# implant9.net
KiCad netlist of a schematic drawn in EAGLE
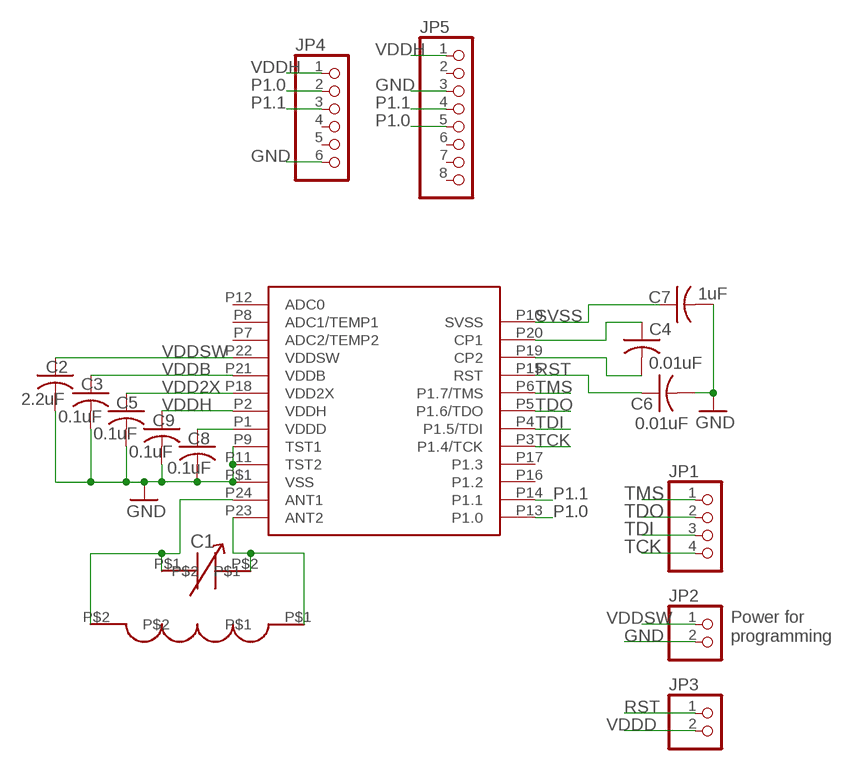
[diagram p0: schematic, sheet 1]

(export (version "E")
  (design (tool "Eeschema 10.0.6"))
  (components
    (comp (ref "C2")
      (value "2.2uF")
      (footprint "eagle-import:C0805")
      (libsource (lib "eagle-import") (part "C-USC0805"))
    )
    (comp (ref "C3")
      (value "0.1uF")
      (footprint "eagle-import:C0805")
      (libsource (lib "eagle-import") (part "C-USC0805"))
    )
    (comp (ref "C4")
      (value "0.01uF")
      (footprint "eagle-import:C0805")
      (libsource (lib "eagle-import") (part "C-USC0805"))
    )
    (comp (ref "C5")
      (value "0.1uF")
      (footprint "eagle-import:C0805")
      (libsource (lib "eagle-import") (part "C-USC0805"))
    )
    (comp (ref "C6")
      (value "0.01uF")
      (footprint "eagle-import:C0805")
      (libsource (lib "eagle-import") (part "C-USC0805"))
    )
    (comp (ref "C7")
      (value "1uF")
      (footprint "eagle-import:C0805")
      (libsource (lib "eagle-import") (part "C-USC0805"))
    )
    (comp (ref "C8")
      (value "0.1uF")
      (footprint "eagle-import:C0805")
      (libsource (lib "eagle-import") (part "C-USC0805"))
    )
    (comp (ref "C9")
      (value "0.1uF")
      (footprint "eagle-import:C0805")
      (libsource (lib "eagle-import") (part "C-USC0805"))
    )
    (comp (ref "JP1")
      (value "PINHD-1X4")
      (footprint "eagle-import:1X04")
      (libsource (lib "eagle-import") (part "PINHD-1X4"))
    )
    (comp (ref "JP2")
      (value "PINHD-1X2")
      (footprint "eagle-import:1X02")
      (libsource (lib "eagle-import") (part "PINHD-1X2"))
    )
    (comp (ref "JP3")
      (value "PINHD-1X2")
      (footprint "eagle-import:1X02")
      (libsource (lib "eagle-import") (part "PINHD-1X2"))
    )
    (comp (ref "JP4")
      (value "PINHD-1X6")
      (footprint "eagle-import:1X06")
      (libsource (lib "eagle-import") (part "PINHD-1X6"))
    )
    (comp (ref "JP5")
      (value "PINHD-1X8")
      (footprint "eagle-import:1X08")
      (libsource (lib "eagle-import") (part "PINHD-1X8"))
    )
    (comp (ref "U$1")
      (value "RF430FRL152H")
      (footprint "eagle-import:VQFN")
      (libsource (lib "eagle-import") (part "RF430FRL152H"))
    )
    (comp (ref "U$2")
      (value "COILCOIL3")
      (footprint "eagle-import:COIL3")
      (libsource (lib "eagle-import") (part "COILCOIL3"))
    )
    (comp (ref "U$3")
      (value "VAR_CAP")
      (footprint "eagle-import:VAR_CAP")
      (libsource (lib "eagle-import") (part "VAR_CAP"))
    )
  )
  (nets
    (net (code "1") (name "/P1.0") (class "Default")
      (node (ref "JP4") (pin "2") (pinfunction "2_2") (pintype "passive"))
      (node (ref "JP5") (pin "5") (pinfunction "5_5") (pintype "passive"))
      (node (ref "U$1") (pin "P13") (pinfunction "P1.0_P13") (pintype "bidirectional"))
    )
    (net (code "2") (name "/P1.1") (class "Default")
      (node (ref "JP4") (pin "3") (pinfunction "3_3") (pintype "passive"))
      (node (ref "JP5") (pin "4") (pinfunction "4_4") (pintype "passive"))
      (node (ref "U$1") (pin "P14") (pinfunction "P1.1_P14") (pintype "bidirectional"))
    )
    (net (code "3") (name "/RST") (class "Default")
      (node (ref "C6") (pin "1") (pinfunction "1_1") (pintype "passive"))
      (node (ref "JP3") (pin "1") (pinfunction "1_1") (pintype "passive"))
      (node (ref "U$1") (pin "P15") (pinfunction "RST_P15") (pintype "bidirectional"))
    )
    (net (code "4") (name "/SVSS") (class "Default")
      (node (ref "C7") (pin "1") (pinfunction "1_1") (pintype "passive"))
      (node (ref "U$1") (pin "P10") (pinfunction "SVSS_P10") (pintype "bidirectional"))
    )
    (net (code "5") (name "/TCK") (class "Default")
      (node (ref "JP1") (pin "4") (pinfunction "4_4") (pintype "passive"))
      (node (ref "U$1") (pin "P3") (pinfunction "P1.4/TCK_P3") (pintype "bidirectional"))
    )
    (net (code "6") (name "/TDI") (class "Default")
      (node (ref "JP1") (pin "3") (pinfunction "3_3") (pintype "passive"))
      (node (ref "U$1") (pin "P4") (pinfunction "P1.5/TDI_P4") (pintype "bidirectional"))
    )
    (net (code "7") (name "/TDO") (class "Default")
      (node (ref "JP1") (pin "2") (pinfunction "2_2") (pintype "passive"))
      (node (ref "U$1") (pin "P5") (pinfunction "P1.6/TDO_P5") (pintype "bidirectional"))
    )
    (net (code "8") (name "/TMS") (class "Default")
      (node (ref "JP1") (pin "1") (pinfunction "1_1") (pintype "passive"))
      (node (ref "U$1") (pin "P6") (pinfunction "P1.7/TMS_P6") (pintype "bidirectional"))
    )
    (net (code "9") (name "/VDD2X") (class "Default")
      (node (ref "C5") (pin "1") (pinfunction "1_1") (pintype "passive"))
      (node (ref "U$1") (pin "P18") (pinfunction "VDD2X_P18") (pintype "bidirectional"))
    )
    (net (code "10") (name "/VDDB") (class "Default")
      (node (ref "C3") (pin "1") (pinfunction "1_1") (pintype "passive"))
      (node (ref "U$1") (pin "P21") (pinfunction "VDDB_P21") (pintype "bidirectional"))
    )
    (net (code "11") (name "/VDDD") (class "Default")
      (node (ref "C8") (pin "1") (pinfunction "1_1") (pintype "passive"))
      (node (ref "JP3") (pin "2") (pinfunction "2_2") (pintype "passive"))
      (node (ref "U$1") (pin "P1") (pinfunction "VDDD_P1") (pintype "bidirectional"))
    )
    (net (code "12") (name "/VDDH") (class "Default")
      (node (ref "C9") (pin "1") (pinfunction "1_1") (pintype "passive"))
      (node (ref "JP4") (pin "1") (pinfunction "1_1") (pintype "passive"))
      (node (ref "JP5") (pin "1") (pinfunction "1_1") (pintype "passive"))
      (node (ref "U$1") (pin "P2") (pinfunction "VDDH_P2") (pintype "bidirectional"))
    )
    (net (code "13") (name "/VDDSW") (class "Default")
      (node (ref "C2") (pin "1") (pinfunction "1_1") (pintype "passive"))
      (node (ref "JP2") (pin "1") (pinfunction "1_1") (pintype "passive"))
      (node (ref "U$1") (pin "P22") (pinfunction "VDDSW_P22") (pintype "bidirectional"))
    )
    (net (code "14") (name "GND") (class "Default")
      (node (ref "C2") (pin "2") (pinfunction "2_2") (pintype "passive"))
      (node (ref "C3") (pin "2") (pinfunction "2_2") (pintype "passive"))
      (node (ref "C5") (pin "2") (pinfunction "2_2") (pintype "passive"))
      (node (ref "C6") (pin "2") (pinfunction "2_2") (pintype "passive"))
      (node (ref "C7") (pin "2") (pinfunction "2_2") (pintype "passive"))
      (node (ref "C8") (pin "2") (pinfunction "2_2") (pintype "passive"))
      (node (ref "C9") (pin "2") (pinfunction "2_2") (pintype "passive"))
      (node (ref "JP2") (pin "2") (pinfunction "2_2") (pintype "passive"))
      (node (ref "JP4") (pin "6") (pinfunction "6_6") (pintype "passive"))
      (node (ref "JP5") (pin "3") (pinfunction "3_3") (pintype "passive"))
      (node (ref "U$1") (pin "P$1") (pinfunction "VSS_P$1") (pintype "bidirectional"))
      (node (ref "U$1") (pin "P11") (pinfunction "TST2_P11") (pintype "bidirectional"))
      (node (ref "U$1") (pin "P9") (pinfunction "TST1_P9") (pintype "bidirectional"))
    )
    (net (code "15") (name "Net-(U$1-ANT1)") (class "Default")
      (node (ref "U$1") (pin "P24") (pinfunction "ANT1_P24") (pintype "bidirectional"))
      (node (ref "U$2") (pin "P$2") (pinfunction "P$2_P$2") (pintype "bidirectional"))
      (node (ref "U$3") (pin "P$1") (pinfunction "P$1_P$1") (pintype "bidirectional"))
    )
    (net (code "16") (name "Net-(U$1-ANT2)") (class "Default")
      (node (ref "U$1") (pin "P23") (pinfunction "ANT2_P23") (pintype "bidirectional"))
      (node (ref "U$2") (pin "P$1") (pinfunction "P$1_P$1") (pintype "bidirectional"))
      (node (ref "U$3") (pin "P$2") (pinfunction "P$2_P$2") (pintype "bidirectional"))
    )
    (net (code "17") (name "Net-(U$1-CP1)") (class "Default")
      (node (ref "C4") (pin "1") (pinfunction "1_1") (pintype "passive"))
      (node (ref "U$1") (pin "P20") (pinfunction "CP1_P20") (pintype "bidirectional"))
    )
    (net (code "18") (name "Net-(U$1-CP2)") (class "Default")
      (node (ref "C4") (pin "2") (pinfunction "2_2") (pintype "passive"))
      (node (ref "U$1") (pin "P19") (pinfunction "CP2_P19") (pintype "bidirectional"))
    )
    (net (code "19") (name "unconnected-(JP4-Pad4)") (class "Default")
      (node (ref "JP4") (pin "4") (pinfunction "4_4") (pintype "passive"))
    )
    (net (code "20") (name "unconnected-(JP4-Pad5)") (class "Default")
      (node (ref "JP4") (pin "5") (pinfunction "5_5") (pintype "passive"))
    )
    (net (code "21") (name "unconnected-(JP5-Pad2)") (class "Default")
      (node (ref "JP5") (pin "2") (pinfunction "2_2") (pintype "passive"))
    )
    (net (code "22") (name "unconnected-(JP5-Pad6)") (class "Default")
      (node (ref "JP5") (pin "6") (pinfunction "6_6") (pintype "passive"))
    )
    (net (code "23") (name "unconnected-(JP5-Pad7)") (class "Default")
      (node (ref "JP5") (pin "7") (pinfunction "7_7") (pintype "passive"))
    )
    (net (code "24") (name "unconnected-(JP5-Pad8)") (class "Default")
      (node (ref "JP5") (pin "8") (pinfunction "8_8") (pintype "passive"))
    )
    (net (code "25") (name "unconnected-(U$1-ADC0-PadP12)") (class "Default")
      (node (ref "U$1") (pin "P12") (pinfunction "ADC0_P12") (pintype "bidirectional"))
    )
    (net (code "26") (name "unconnected-(U$1-ADC1{slash}TEMP1-PadP8)") (class "Default")
      (node (ref "U$1") (pin "P8") (pinfunction "ADC1/TEMP1_P8") (pintype "bidirectional"))
    )
    (net (code "27") (name "unconnected-(U$1-ADC2{slash}TEMP2-PadP7)") (class "Default")
      (node (ref "U$1") (pin "P7") (pinfunction "ADC2/TEMP2_P7") (pintype "bidirectional"))
    )
    (net (code "28") (name "unconnected-(U$1-P1.2-PadP16)") (class "Default")
      (node (ref "U$1") (pin "P16") (pinfunction "P1.2_P16") (pintype "bidirectional"))
    )
    (net (code "29") (name "unconnected-(U$1-P1.3-PadP17)") (class "Default")
      (node (ref "U$1") (pin "P17") (pinfunction "P1.3_P17") (pintype "bidirectional"))
    )
  )
)
